# 5V_Sheet.net
KiCad netlist of a schematic drawn in Altium Designer
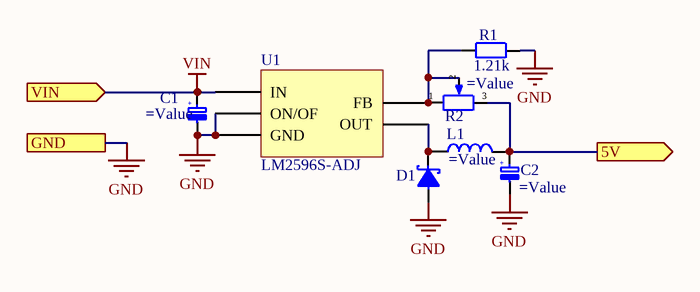
[diagram p0: 5V Sheet.SchDoc]

(export (version "E")
  (design (tool "Eeschema 10.0.6"))
  (components
    (comp (ref "C1")
      (value "~")
      (footprint "D8C3.2H12")
      (libsource (lib "AlexChistiakov") (part "Cap Tantal"))
    )
    (comp (ref "C2")
      (value "~")
      (footprint "D8C3.2H12")
      (libsource (lib "AlexChistiakov") (part "Cap Electrolytic"))
    )
    (comp (ref "D1")
      (value "MBRS340T3G")
      (footprint "DO214AB(SMC)")
      (libsource (lib "AlexChistiakov") (part "MBRS340T3G"))
    )
    (comp (ref "L1") (value "~") (footprint "SRR1280") (libsource (lib "AlexChistiakov") (part "Inductor")))
    (comp (ref "R1")
      (value "1.21k")
      (footprint "res0603")
      (libsource (lib "Discrete smd") (part "Resistor SMD"))
    )
    (comp (ref "R2")
      (value "~")
      (footprint "3224W")
      (libsource (lib "AlexChistiakov") (part "Potentiometer"))
    )
    (comp (ref "U1")
      (value "LM2596S-ADJ")
      (footprint "TO263-5L")
      (libsource (lib "AlexChistiakov") (part "LM2596S-ADJ"))
    )
  )
  (nets
    (net (code "1") (name "/5V") (class "Default")
      (node (ref "C2") (pin "1") (pinfunction "PLUS_1") (pintype "passive"))
      (node (ref "L1") (pin "2") (pinfunction "2_2") (pintype "passive"))
      (node (ref "R2") (pin "3") (pinfunction "3_3") (pintype "passive"))
    )
    (net (code "2") (name "GND") (class "Default")
      (node (ref "C1") (pin "1") (pinfunction "MINUS_1") (pintype "passive"))
      (node (ref "C2") (pin "2") (pinfunction "MINUS_2") (pintype "passive"))
      (node (ref "D1") (pin "1") (pinfunction "1_1") (pintype "passive"))
      (node (ref "R1") (pin "2") (pinfunction "2_2") (pintype "passive"))
      (node (ref "U1") (pin "3") (pinfunction "GND_3") (pintype "passive"))
      (node (ref "U1") (pin "5") (pinfunction "ON/OF_5") (pintype "passive"))
    )
    (net (code "3") (name "Net-(U1-FB)") (class "Default")
      (node (ref "R1") (pin "1") (pinfunction "1_1") (pintype "passive"))
      (node (ref "R2") (pin "1") (pinfunction "1_1") (pintype "passive"))
      (node (ref "R2") (pin "2") (pinfunction "2_2") (pintype "passive"))
      (node (ref "U1") (pin "4") (pinfunction "FB_4") (pintype "passive"))
    )
    (net (code "4") (name "Net-(U1-OUT)") (class "Default")
      (node (ref "D1") (pin "2") (pinfunction "2_2") (pintype "passive"))
      (node (ref "L1") (pin "1") (pinfunction "1_1") (pintype "passive"))
      (node (ref "U1") (pin "2") (pinfunction "OUT_2") (pintype "passive"))
    )
    (net (code "5") (name "VIN") (class "Default")
      (node (ref "C1") (pin "2") (pinfunction "PLUS_2") (pintype "passive"))
      (node (ref "U1") (pin "1") (pinfunction "IN_1") (pintype "passive"))
    )
  )
)
